# SchematicPULPiniMCU_V1.net
KiCad netlist of a schematic drawn in Altium Designer
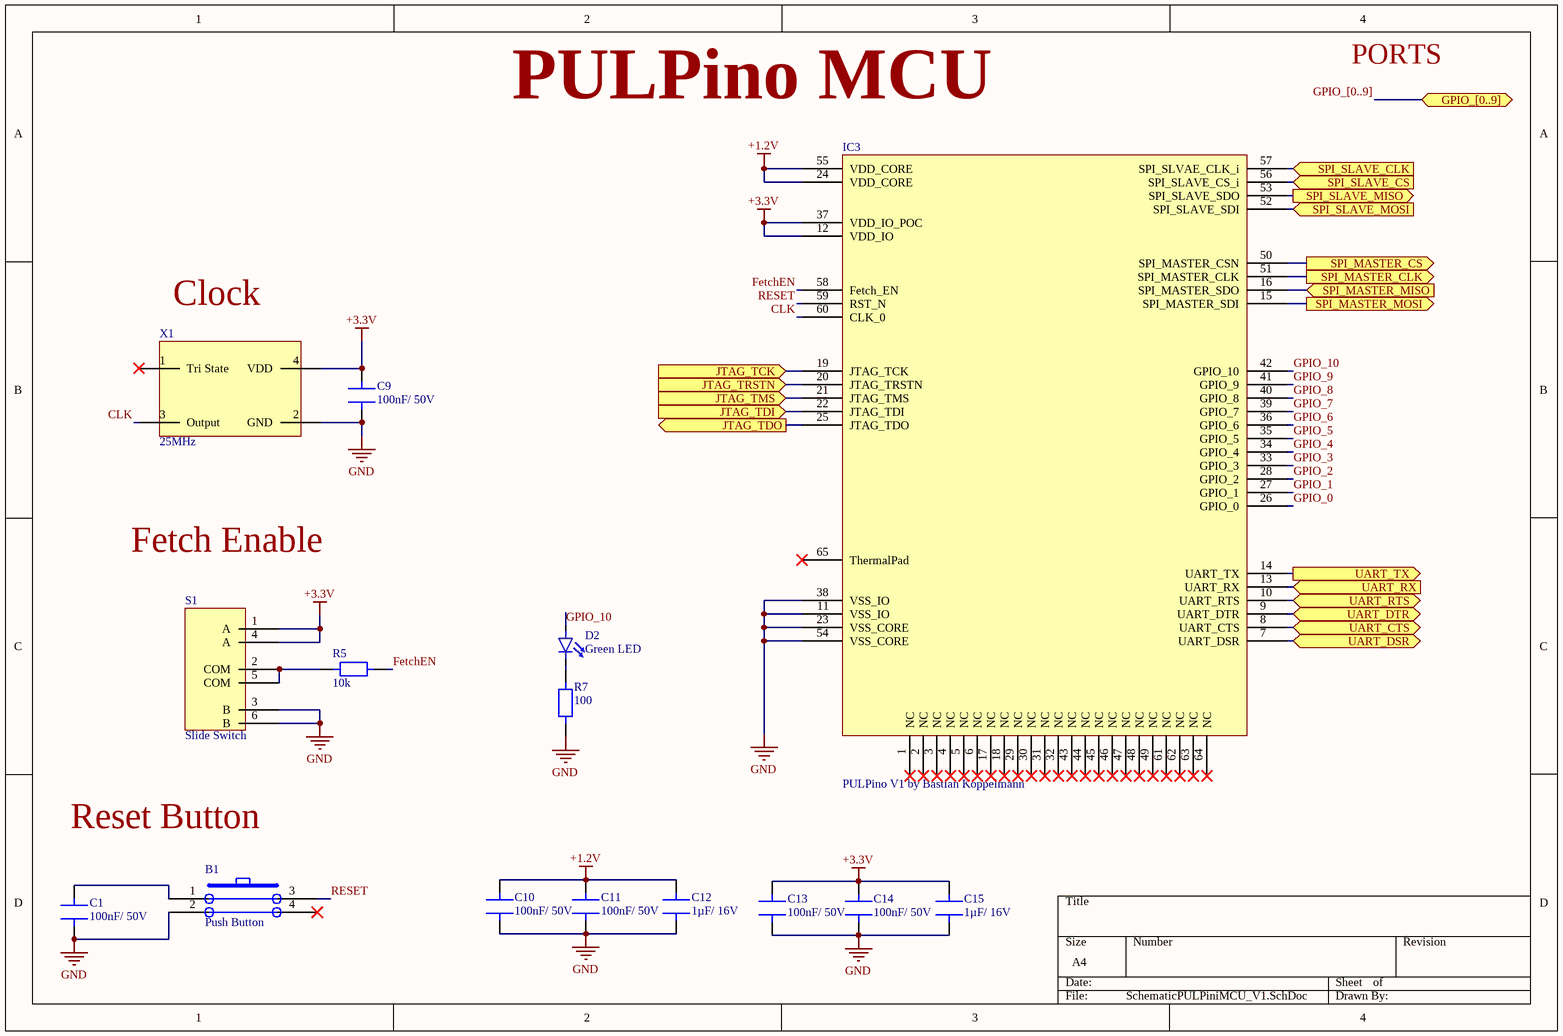
[diagram p0: SchematicPULPiniMCU_V1.SchDoc]

(export (version "E")
  (design (tool "Eeschema 10.0.6"))
  (components
    (comp (ref "B1")
      (value "Push Button")
      (footprint "PUSH Switch")
      (description "PTS647SM50SMTR2LFS")
      (libsource (lib "upbracing_library") (part "Push Button PTS647SM50SMTR2LFS"))
    )
    (comp (ref "C1")
      (value "100nF/ 50V")
      (footprint "C0603")
      (description "C0603/C0805")
      (libsource (lib "upbracing_library") (part "C 100nF/ 50V"))
    )
    (comp (ref "C9")
      (value "100nF/ 50V")
      (footprint "C0603")
      (description "C0603/C0805")
      (libsource (lib "upbracing_library") (part "C 100nF/ 50V"))
    )
    (comp (ref "C10")
      (value "100nF/ 50V")
      (footprint "C0603")
      (description "C0603/C0805")
      (libsource (lib "upbracing_library") (part "C 100nF/ 50V"))
    )
    (comp (ref "C11")
      (value "100nF/ 50V")
      (footprint "C0603")
      (description "C0603/C0805")
      (libsource (lib "upbracing_library") (part "C 100nF/ 50V"))
    )
    (comp (ref "C12")
      (value "1µF/ 16V")
      (footprint "C0603")
      (description "C0603/C0805")
      (libsource (lib "upbracing_library") (part "C 1µF/ 16V"))
    )
    (comp (ref "C13")
      (value "100nF/ 50V")
      (footprint "C0603")
      (description "C0603/C0805")
      (libsource (lib "upbracing_library") (part "C 100nF/ 50V"))
    )
    (comp (ref "C14")
      (value "100nF/ 50V")
      (footprint "C0603")
      (description "C0603/C0805")
      (libsource (lib "upbracing_library") (part "C 100nF/ 50V"))
    )
    (comp (ref "C15")
      (value "1µF/ 16V")
      (footprint "C0603")
      (description "C0603/C0805")
      (libsource (lib "upbracing_library") (part "C 1µF/ 16V"))
    )
    (comp (ref "D2")
      (value "Green LED")
      (footprint "LED_0805")
      (description "Status LED")
      (libsource (lib "upbracing_library") (part "LED 0805"))
    )
    (comp (ref "IC3")
      (value "PULPino V1 by Bastian Koppelmann")
      (footprint "MQFN 64-Lead 9mm P=0.5mm")
      (description "Version 1 PULPino by Bastian Koppelmann")
      (libsource (lib "upbracing_library") (part "MCU PULPino V1 QFN64"))
    )
    (comp (ref "R5")
      (value "10k")
      (footprint "R0603")
      (description "0805")
      (libsource (lib "upbracing_library") (part "RES_10k"))
    )
    (comp (ref "R7")
      (value "100")
      (footprint "R0603")
      (description "0603/0805")
      (libsource (lib "upbracing_library") (part "RES_100"))
    )
    (comp (ref "S1")
      (value "Slide Switch")
      (footprint "Slide Switch WE 452403012014")
      (description "Slide Switch, WE 452403012014")
      (libsource (lib "upbracing_library") (part "Slide Switch WE 452403012014"))
    )
    (comp (ref "X1")
      (value "25MHz")
      (footprint "TCXO Oscillators ECS-TXO-2016-1601065")
      (description "Oscillator 25MHz")
      (libsource (lib "upbracing_library") (part "ECS-TXO-2016-33-250-TR"))
    )
  )
  (nets
    (net (code "1") (name "+1.2V") (class "Default")
      (node (ref "C10") (pin "2") (pinfunction "2_2") (pintype "passive"))
      (node (ref "C11") (pin "2") (pinfunction "2_2") (pintype "passive"))
      (node (ref "C12") (pin "2") (pinfunction "2_2") (pintype "passive"))
      (node (ref "IC3") (pin "24") (pinfunction "VDD_CORE_24") (pintype "passive"))
      (node (ref "IC3") (pin "55") (pinfunction "VDD_CORE_55") (pintype "passive"))
    )
    (net (code "2") (name "+3.3V") (class "Default")
      (node (ref "C13") (pin "2") (pinfunction "2_2") (pintype "passive"))
      (node (ref "C14") (pin "2") (pinfunction "2_2") (pintype "passive"))
      (node (ref "C15") (pin "2") (pinfunction "2_2") (pintype "passive"))
      (node (ref "C9") (pin "1") (pinfunction "1_1") (pintype "passive"))
      (node (ref "IC3") (pin "12") (pinfunction "VDD_IO_12") (pintype "passive"))
      (node (ref "IC3") (pin "37") (pinfunction "VDD_IO_POC_37") (pintype "passive"))
      (node (ref "S1") (pin "1") (pinfunction "A_1") (pintype "passive"))
      (node (ref "S1") (pin "4") (pinfunction "A_4") (pintype "passive"))
      (node (ref "X1") (pin "4") (pinfunction "VDD_4") (pintype "passive"))
    )
    (net (code "3") (name "/CLK") (class "Default")
      (node (ref "IC3") (pin "60") (pinfunction "CLK_0_60") (pintype "passive"))
      (node (ref "X1") (pin "3") (pinfunction "Output_3") (pintype "passive"))
    )
    (net (code "4") (name "/FetchEN") (class "Default")
      (node (ref "IC3") (pin "58") (pinfunction "Fetch_EN_58") (pintype "passive"))
      (node (ref "R5") (pin "2") (pinfunction "2_2") (pintype "passive"))
    )
    (net (code "5") (name "/GPIO_0") (class "Default")
      (node (ref "IC3") (pin "26") (pinfunction "GPIO_0_26") (pintype "passive"))
    )
    (net (code "6") (name "/GPIO_1") (class "Default")
      (node (ref "IC3") (pin "27") (pinfunction "GPIO_1_27") (pintype "passive"))
    )
    (net (code "7") (name "/GPIO_2") (class "Default")
      (node (ref "IC3") (pin "28") (pinfunction "GPIO_2_28") (pintype "passive"))
    )
    (net (code "8") (name "/GPIO_3") (class "Default")
      (node (ref "IC3") (pin "33") (pinfunction "GPIO_3_33") (pintype "passive"))
    )
    (net (code "9") (name "/GPIO_4") (class "Default")
      (node (ref "IC3") (pin "34") (pinfunction "GPIO_4_34") (pintype "passive"))
    )
    (net (code "10") (name "/GPIO_5") (class "Default")
      (node (ref "IC3") (pin "35") (pinfunction "GPIO_5_35") (pintype "passive"))
    )
    (net (code "11") (name "/GPIO_6") (class "Default")
      (node (ref "IC3") (pin "36") (pinfunction "GPIO_6_36") (pintype "passive"))
    )
    (net (code "12") (name "/GPIO_7") (class "Default")
      (node (ref "IC3") (pin "39") (pinfunction "GPIO_7_39") (pintype "passive"))
    )
    (net (code "13") (name "/GPIO_8") (class "Default")
      (node (ref "IC3") (pin "40") (pinfunction "GPIO_8_40") (pintype "passive"))
    )
    (net (code "14") (name "/GPIO_9") (class "Default")
      (node (ref "IC3") (pin "41") (pinfunction "GPIO_9_41") (pintype "passive"))
    )
    (net (code "15") (name "/GPIO_10") (class "Default")
      (node (ref "D2") (pin "1") (pinfunction "1_1") (pintype "passive"))
      (node (ref "IC3") (pin "42") (pinfunction "GPIO_10_42") (pintype "passive"))
    )
    (net (code "17") (name "/JTAG_TCK") (class "Default")
      (node (ref "IC3") (pin "19") (pinfunction "JTAG_TCK_19") (pintype "passive"))
    )
    (net (code "18") (name "/JTAG_TDI") (class "Default")
      (node (ref "IC3") (pin "22") (pinfunction "JTAG_TDI_22") (pintype "passive"))
    )
    (net (code "19") (name "/JTAG_TDO") (class "Default")
      (node (ref "IC3") (pin "25") (pinfunction "JTAG_TDO_25") (pintype "passive"))
    )
    (net (code "20") (name "/JTAG_TMS") (class "Default")
      (node (ref "IC3") (pin "21") (pinfunction "JTAG_TMS_21") (pintype "passive"))
    )
    (net (code "21") (name "/JTAG_TRSTN") (class "Default")
      (node (ref "IC3") (pin "20") (pinfunction "JTAG_TRSTN_20") (pintype "passive"))
    )
    (net (code "22") (name "/RESET") (class "Default")
      (node (ref "B1") (pin "3") (pinfunction "1_3") (pintype "passive"))
      (node (ref "IC3") (pin "59") (pinfunction "RST_N_59") (pintype "passive"))
    )
    (net (code "23") (name "/SPI_MASTER_CLK") (class "Default")
      (node (ref "IC3") (pin "51") (pinfunction "SPI_MASTER_CLK_51") (pintype "passive"))
    )
    (net (code "24") (name "/SPI_MASTER_CS") (class "Default")
      (node (ref "IC3") (pin "50") (pinfunction "SPI_MASTER_CSN_50") (pintype "passive"))
    )
    (net (code "25") (name "/SPI_MASTER_MISO") (class "Default")
      (node (ref "IC3") (pin "16") (pinfunction "SPI_MASTER_SDO_16") (pintype "passive"))
    )
    (net (code "26") (name "/SPI_MASTER_MOSI") (class "Default")
      (node (ref "IC3") (pin "15") (pinfunction "SPI_MASTER_SDI_15") (pintype "passive"))
    )
    (net (code "27") (name "/SPI_SLAVE_CLK") (class "Default")
      (node (ref "IC3") (pin "57") (pinfunction "SPI_SLVAE_CLK_i_57") (pintype "passive"))
    )
    (net (code "28") (name "/SPI_SLAVE_CS") (class "Default")
      (node (ref "IC3") (pin "56") (pinfunction "SPI_SLAVE_CS_i_56") (pintype "passive"))
    )
    (net (code "29") (name "/SPI_SLAVE_MISO") (class "Default")
      (node (ref "IC3") (pin "53") (pinfunction "SPI_SLAVE_SDO_53") (pintype "passive"))
    )
    (net (code "30") (name "/SPI_SLAVE_MOSI") (class "Default")
      (node (ref "IC3") (pin "52") (pinfunction "SPI_SLAVE_SDI_52") (pintype "passive"))
    )
    (net (code "31") (name "/UART_CTS") (class "Default")
      (node (ref "IC3") (pin "8") (pinfunction "UART_CTS_8") (pintype "passive"))
    )
    (net (code "32") (name "/UART_DSR") (class "Default")
      (node (ref "IC3") (pin "7") (pinfunction "UART_DSR_7") (pintype "passive"))
    )
    (net (code "33") (name "/UART_DTR") (class "Default")
      (node (ref "IC3") (pin "9") (pinfunction "UART_DTR_9") (pintype "passive"))
    )
    (net (code "34") (name "/UART_RTS") (class "Default")
      (node (ref "IC3") (pin "10") (pinfunction "UART_RTS_10") (pintype "passive"))
    )
    (net (code "35") (name "/UART_RX") (class "Default")
      (node (ref "IC3") (pin "13") (pinfunction "UART_RX_13") (pintype "passive"))
    )
    (net (code "36") (name "/UART_TX") (class "Default")
      (node (ref "IC3") (pin "14") (pinfunction "UART_TX_14") (pintype "passive"))
    )
    (net (code "37") (name "GND") (class "Default")
      (node (ref "B1") (pin "2") (pinfunction "2_2") (pintype "passive"))
      (node (ref "C1") (pin "2") (pinfunction "2_2") (pintype "passive"))
      (node (ref "C10") (pin "1") (pinfunction "1_1") (pintype "passive"))
      (node (ref "C11") (pin "1") (pinfunction "1_1") (pintype "passive"))
      (node (ref "C12") (pin "1") (pinfunction "1_1") (pintype "passive"))
      (node (ref "C13") (pin "1") (pinfunction "1_1") (pintype "passive"))
      (node (ref "C14") (pin "1") (pinfunction "1_1") (pintype "passive"))
      (node (ref "C15") (pin "1") (pinfunction "1_1") (pintype "passive"))
      (node (ref "C9") (pin "2") (pinfunction "2_2") (pintype "passive"))
      (node (ref "IC3") (pin "11") (pinfunction "VSS_IO_11") (pintype "passive"))
      (node (ref "IC3") (pin "23") (pinfunction "VSS_CORE_23") (pintype "passive"))
      (node (ref "IC3") (pin "38") (pinfunction "VSS_IO_38") (pintype "passive"))
      (node (ref "IC3") (pin "54") (pinfunction "VSS_CORE_54") (pintype "passive"))
      (node (ref "R7") (pin "1") (pinfunction "1_1") (pintype "passive"))
      (node (ref "S1") (pin "3") (pinfunction "B_3") (pintype "passive"))
      (node (ref "S1") (pin "6") (pinfunction "B_6") (pintype "passive"))
      (node (ref "X1") (pin "2") (pinfunction "GND_2") (pintype "passive"))
    )
    (net (code "38") (name "Net-(B1-Pad1)") (class "Default")
      (node (ref "B1") (pin "1") (pinfunction "1_1") (pintype "passive"))
      (node (ref "C1") (pin "1") (pinfunction "1_1") (pintype "passive"))
    )
    (net (code "39") (name "Net-(D2-Pad2)") (class "Default")
      (node (ref "D2") (pin "2") (pinfunction "2_2") (pintype "passive"))
      (node (ref "R7") (pin "2") (pinfunction "2_2") (pintype "passive"))
    )
    (net (code "40") (name "Net-(R5-Pad1)") (class "Default")
      (node (ref "R5") (pin "1") (pinfunction "1_1") (pintype "passive"))
      (node (ref "S1") (pin "2") (pinfunction "COM_2") (pintype "passive"))
      (node (ref "S1") (pin "5") (pinfunction "COM_5") (pintype "passive"))
    )
    (net (code "41") (name "unconnected-(B1-2-Pad4)") (class "Default")
      (node (ref "B1") (pin "4") (pinfunction "2_4") (pintype "passive+no_connect"))
    )
    (net (code "42") (name "unconnected-(IC3-NC-Pad1)") (class "Default")
      (node (ref "IC3") (pin "1") (pinfunction "NC_1") (pintype "passive+no_connect"))
    )
    (net (code "43") (name "unconnected-(IC3-NC-Pad2)") (class "Default")
      (node (ref "IC3") (pin "2") (pinfunction "NC_2") (pintype "passive+no_connect"))
    )
    (net (code "44") (name "unconnected-(IC3-NC-Pad3)") (class "Default")
      (node (ref "IC3") (pin "3") (pinfunction "NC_3") (pintype "passive+no_connect"))
    )
    (net (code "45") (name "unconnected-(IC3-NC-Pad4)") (class "Default")
      (node (ref "IC3") (pin "4") (pinfunction "NC_4") (pintype "passive+no_connect"))
    )
    (net (code "46") (name "unconnected-(IC3-NC-Pad5)") (class "Default")
      (node (ref "IC3") (pin "5") (pinfunction "NC_5") (pintype "passive+no_connect"))
    )
    (net (code "47") (name "unconnected-(IC3-NC-Pad6)") (class "Default")
      (node (ref "IC3") (pin "6") (pinfunction "NC_6") (pintype "passive+no_connect"))
    )
    (net (code "48") (name "unconnected-(IC3-NC-Pad17)") (class "Default")
      (node (ref "IC3") (pin "17") (pinfunction "NC_17") (pintype "passive+no_connect"))
    )
    (net (code "49") (name "unconnected-(IC3-NC-Pad18)") (class "Default")
      (node (ref "IC3") (pin "18") (pinfunction "NC_18") (pintype "passive+no_connect"))
    )
    (net (code "50") (name "unconnected-(IC3-NC-Pad29)") (class "Default")
      (node (ref "IC3") (pin "29") (pinfunction "NC_29") (pintype "passive+no_connect"))
    )
    (net (code "51") (name "unconnected-(IC3-NC-Pad30)") (class "Default")
      (node (ref "IC3") (pin "30") (pinfunction "NC_30") (pintype "passive+no_connect"))
    )
    (net (code "52") (name "unconnected-(IC3-NC-Pad31)") (class "Default")
      (node (ref "IC3") (pin "31") (pinfunction "NC_31") (pintype "passive+no_connect"))
    )
    (net (code "53") (name "unconnected-(IC3-NC-Pad32)") (class "Default")
      (node (ref "IC3") (pin "32") (pinfunction "NC_32") (pintype "passive+no_connect"))
    )
    (net (code "54") (name "unconnected-(IC3-NC-Pad43)") (class "Default")
      (node (ref "IC3") (pin "43") (pinfunction "NC_43") (pintype "passive+no_connect"))
    )
    (net (code "55") (name "unconnected-(IC3-NC-Pad44)") (class "Default")
      (node (ref "IC3") (pin "44") (pinfunction "NC_44") (pintype "passive+no_connect"))
    )
    (net (code "56") (name "unconnected-(IC3-NC-Pad45)") (class "Default")
      (node (ref "IC3") (pin "45") (pinfunction "NC_45") (pintype "passive+no_connect"))
    )
    (net (code "57") (name "unconnected-(IC3-NC-Pad46)") (class "Default")
      (node (ref "IC3") (pin "46") (pinfunction "NC_46") (pintype "passive+no_connect"))
    )
    (net (code "58") (name "unconnected-(IC3-NC-Pad47)") (class "Default")
      (node (ref "IC3") (pin "47") (pinfunction "NC_47") (pintype "passive+no_connect"))
    )
    (net (code "59") (name "unconnected-(IC3-NC-Pad48)") (class "Default")
      (node (ref "IC3") (pin "48") (pinfunction "NC_48") (pintype "passive+no_connect"))
    )
    (net (code "60") (name "unconnected-(IC3-NC-Pad49)") (class "Default")
      (node (ref "IC3") (pin "49") (pinfunction "NC_49") (pintype "passive+no_connect"))
    )
    (net (code "61") (name "unconnected-(IC3-NC-Pad61)") (class "Default")
      (node (ref "IC3") (pin "61") (pinfunction "NC_61") (pintype "passive+no_connect"))
    )
    (net (code "62") (name "unconnected-(IC3-NC-Pad62)") (class "Default")
      (node (ref "IC3") (pin "62") (pinfunction "NC_62") (pintype "passive+no_connect"))
    )
    (net (code "63") (name "unconnected-(IC3-NC-Pad63)") (class "Default")
      (node (ref "IC3") (pin "63") (pinfunction "NC_63") (pintype "passive+no_connect"))
    )
    (net (code "64") (name "unconnected-(IC3-NC-Pad64)") (class "Default")
      (node (ref "IC3") (pin "64") (pinfunction "NC_64") (pintype "passive+no_connect"))
    )
    (net (code "65") (name "unconnected-(IC3-ThermalPad-Pad65)") (class "Default")
      (node (ref "IC3") (pin "65") (pinfunction "ThermalPad_65") (pintype "passive+no_connect"))
    )
    (net (code "66") (name "unconnected-(X1-Tri_State-Pad1)") (class "Default")
      (node (ref "X1") (pin "1") (pinfunction "Tri_State_1") (pintype "passive+no_connect"))
    )
  )
)
